# breeze.net
KiCad netlist of a schematic drawn in EAGLE
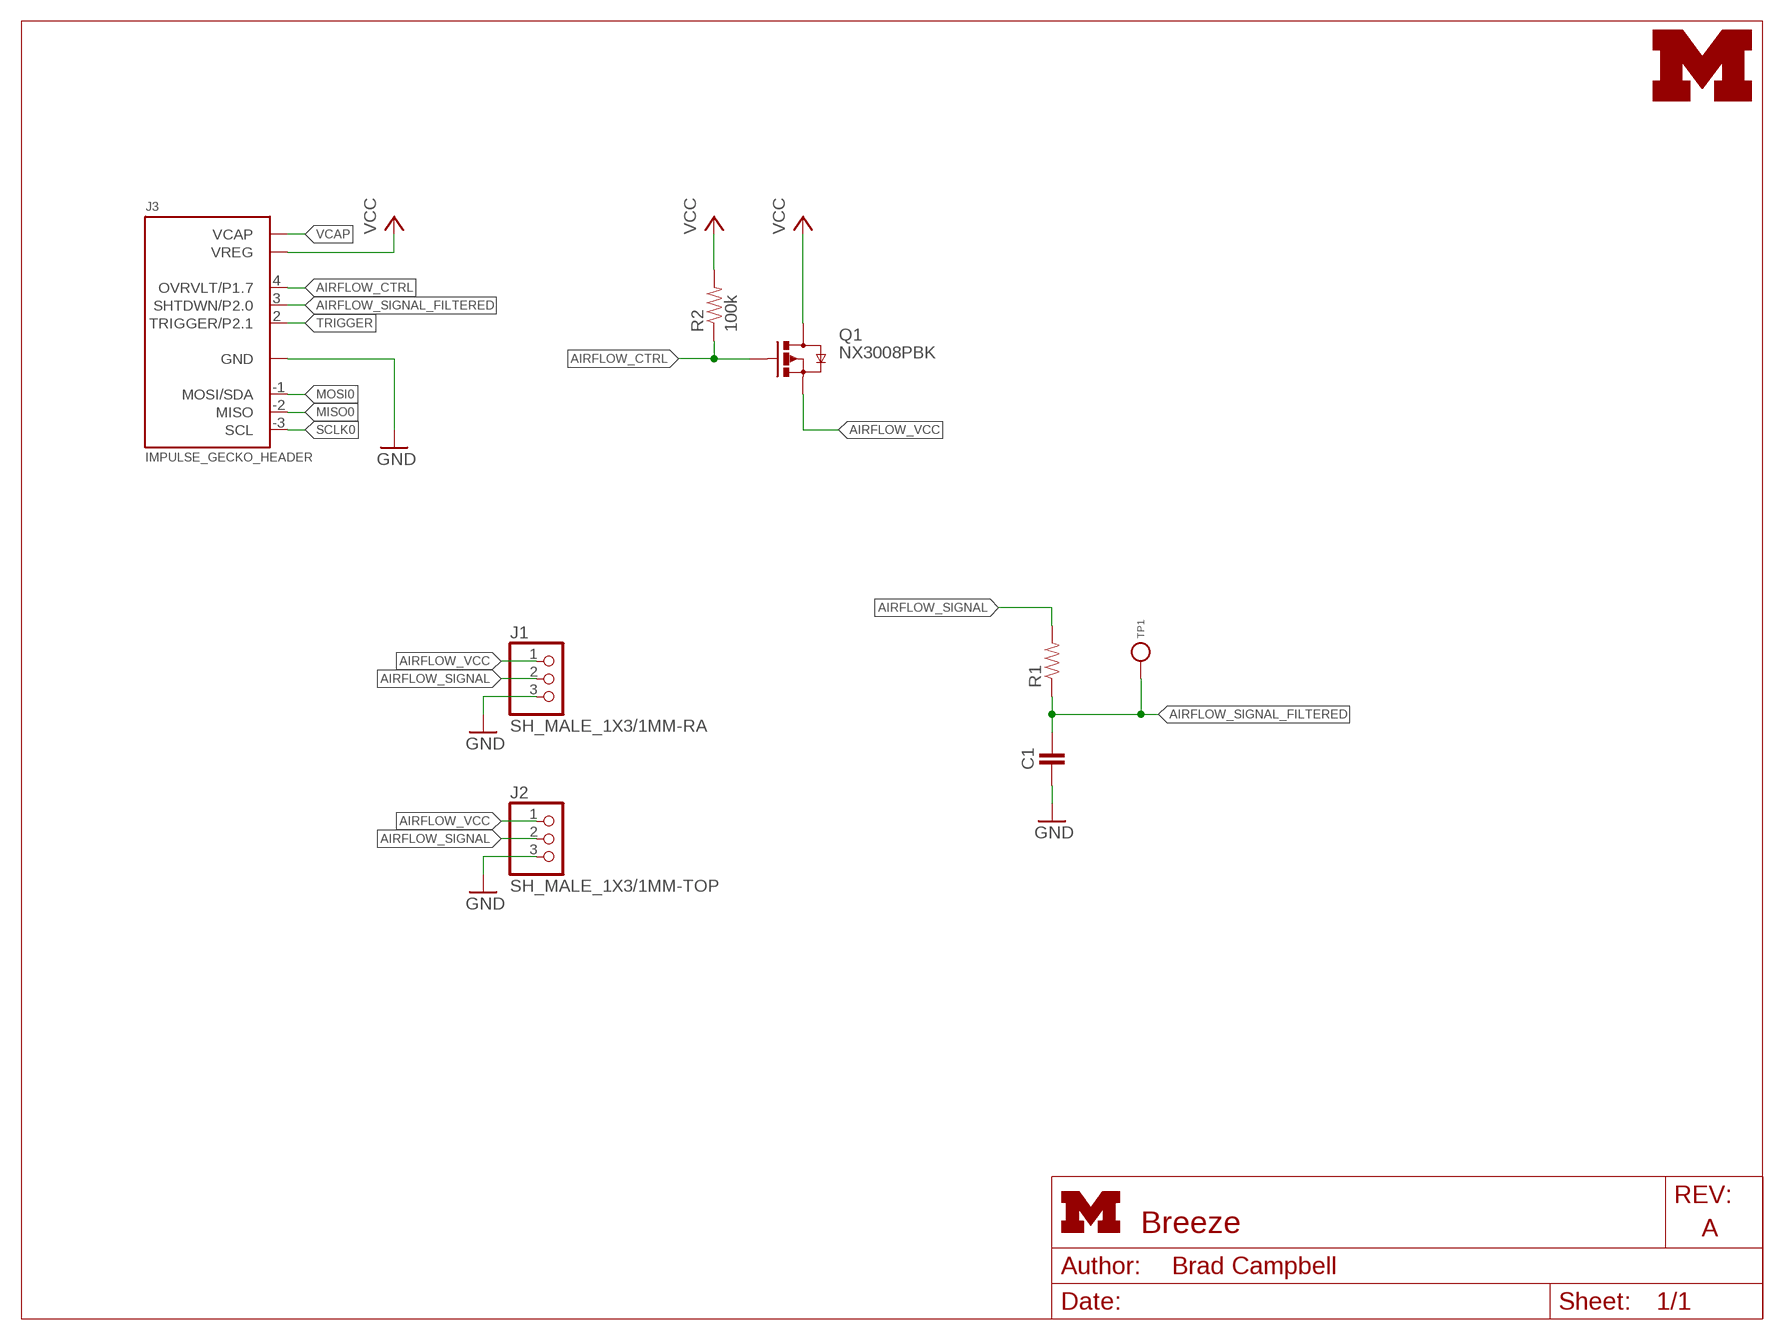
[diagram p0: schematic, sheet 1]

(export (version "E")
  (design (tool "Eeschema 10.0.6"))
  (components
    (comp (ref "C1")
      (value "CAPACITOR")
      (footprint "eagle-import:0402_CAP")
      (libsource (lib "eagle-import") (part "CAPACITOR"))
    )
    (comp (ref "J1")
      (value "SH_MALE_1X3/1MM-RA")
      (footprint "eagle-import:1X3_SMD_SH_RA_1MM")
      (libsource (lib "eagle-import") (part "SH_MALE_1X3/1MM-RA"))
    )
    (comp (ref "J2")
      (value "SH_MALE_1X3/1MM-TOP")
      (footprint "eagle-import:1X3_SMD_SH_1MM")
      (libsource (lib "eagle-import") (part "SH_MALE_1X3/1MM-TOP"))
    )
    (comp (ref "J3")
      (value "IMPULSE_GECKO_HEADER")
      (footprint "eagle-import:HEADER1X9_0.05IN")
      (libsource (lib "eagle-import") (part "IMPULSE_GECKO_HEADER"))
    )
    (comp (ref "LOGO1")
      (value "UMICH_SOLID_TINY")
      (footprint "eagle-import:UMICH_SOLID_50MIL")
      (libsource (lib "eagle-import") (part "UMICH_SOLID_TINY"))
    )
    (comp (ref "Q1")
      (value "NX3008PBK")
      (footprint "eagle-import:SOT23-3")
      (libsource (lib "eagle-import") (part "NX3008PBK"))
    )
    (comp (ref "R1")
      (value "RESISTOR0402_RES")
      (footprint "eagle-import:0402_RES")
      (libsource (lib "eagle-import") (part "RESISTOR0402_RES"))
    )
    (comp (ref "R2")
      (value "100k")
      (footprint "eagle-import:0402_RES")
      (libsource (lib "eagle-import") (part "RESISTOR0402_RES"))
    )
    (comp (ref "TP1")
      (value "TEST_POINT_0.040IN")
      (footprint "eagle-import:TESTPOINT_0.040IN")
      (libsource (lib "eagle-import") (part "TEST_POINT_0.040IN"))
    )
  )
  (nets
    (net (code "1") (name "AIRFLOW_CTRL") (class "Default")
      (node (ref "J3") (pin "4") (pinfunction "OVRVLT/P1.7_4") (pintype "bidirectional"))
      (node (ref "Q1") (pin "1") (pinfunction "G_1") (pintype "passive"))
      (node (ref "R2") (pin "1") (pinfunction "1_1") (pintype "passive"))
    )
    (net (code "2") (name "AIRFLOW_SIGNAL") (class "Default")
      (node (ref "J1") (pin "2") (pinfunction "2_2") (pintype "passive"))
      (node (ref "J2") (pin "2") (pinfunction "2_2") (pintype "passive"))
      (node (ref "R1") (pin "2") (pinfunction "2_2") (pintype "passive"))
    )
    (net (code "3") (name "AIRFLOW_SIGNAL_FILTERED") (class "Default")
      (node (ref "C1") (pin "1") (pinfunction "1_1") (pintype "bidirectional"))
      (node (ref "J3") (pin "3") (pinfunction "SHTDWN/P2.0_3") (pintype "bidirectional"))
      (node (ref "R1") (pin "1") (pinfunction "1_1") (pintype "passive"))
      (node (ref "TP1") (pin "TESTPOINT") (pinfunction "TESTPOINT_TESTPOINT") (pintype "bidirectional"))
    )
    (net (code "4") (name "AIRFLOW_VCC") (class "Default")
      (node (ref "J1") (pin "1") (pinfunction "1_1") (pintype "passive"))
      (node (ref "J2") (pin "1") (pinfunction "1_1") (pintype "passive"))
      (node (ref "Q1") (pin "2") (pinfunction "S_2") (pintype "passive"))
    )
    (net (code "5") (name "GND") (class "Default")
      (node (ref "C1") (pin "2") (pinfunction "2_2") (pintype "bidirectional"))
      (node (ref "J1") (pin "3") (pinfunction "3_3") (pintype "passive"))
      (node (ref "J2") (pin "3") (pinfunction "3_3") (pintype "passive"))
      (node (ref "J3") (pin "0") (pinfunction "GND_0") (pintype "bidirectional"))
    )
    (net (code "6") (name "MISO0") (class "Default")
      (node (ref "J3") (pin "-2") (pinfunction "MISO_-2") (pintype "bidirectional"))
    )
    (net (code "7") (name "MOSI0") (class "Default")
      (node (ref "J3") (pin "-1") (pinfunction "MOSI/SDA_-1") (pintype "bidirectional"))
    )
    (net (code "8") (name "SCLK0") (class "Default")
      (node (ref "J3") (pin "-3") (pinfunction "SCL_-3") (pintype "bidirectional"))
    )
    (net (code "9") (name "TRIGGER") (class "Default")
      (node (ref "J3") (pin "2") (pinfunction "TRIGGER/P2.1_2") (pintype "bidirectional"))
    )
    (net (code "10") (name "VCAP") (class "Default")
      (node (ref "J3") (pin "5") (pinfunction "VCAP_5") (pintype "output"))
    )
    (net (code "11") (name "VCC") (class "Default")
      (node (ref "J3") (pin "1") (pinfunction "VREG_1") (pintype "bidirectional"))
      (node (ref "Q1") (pin "3") (pinfunction "D_3") (pintype "passive"))
      (node (ref "R2") (pin "2") (pinfunction "2_2") (pintype "passive"))
    )
  )
)
